# l297_l298.net
KiCad netlist of a schematic drawn in Altium Designer
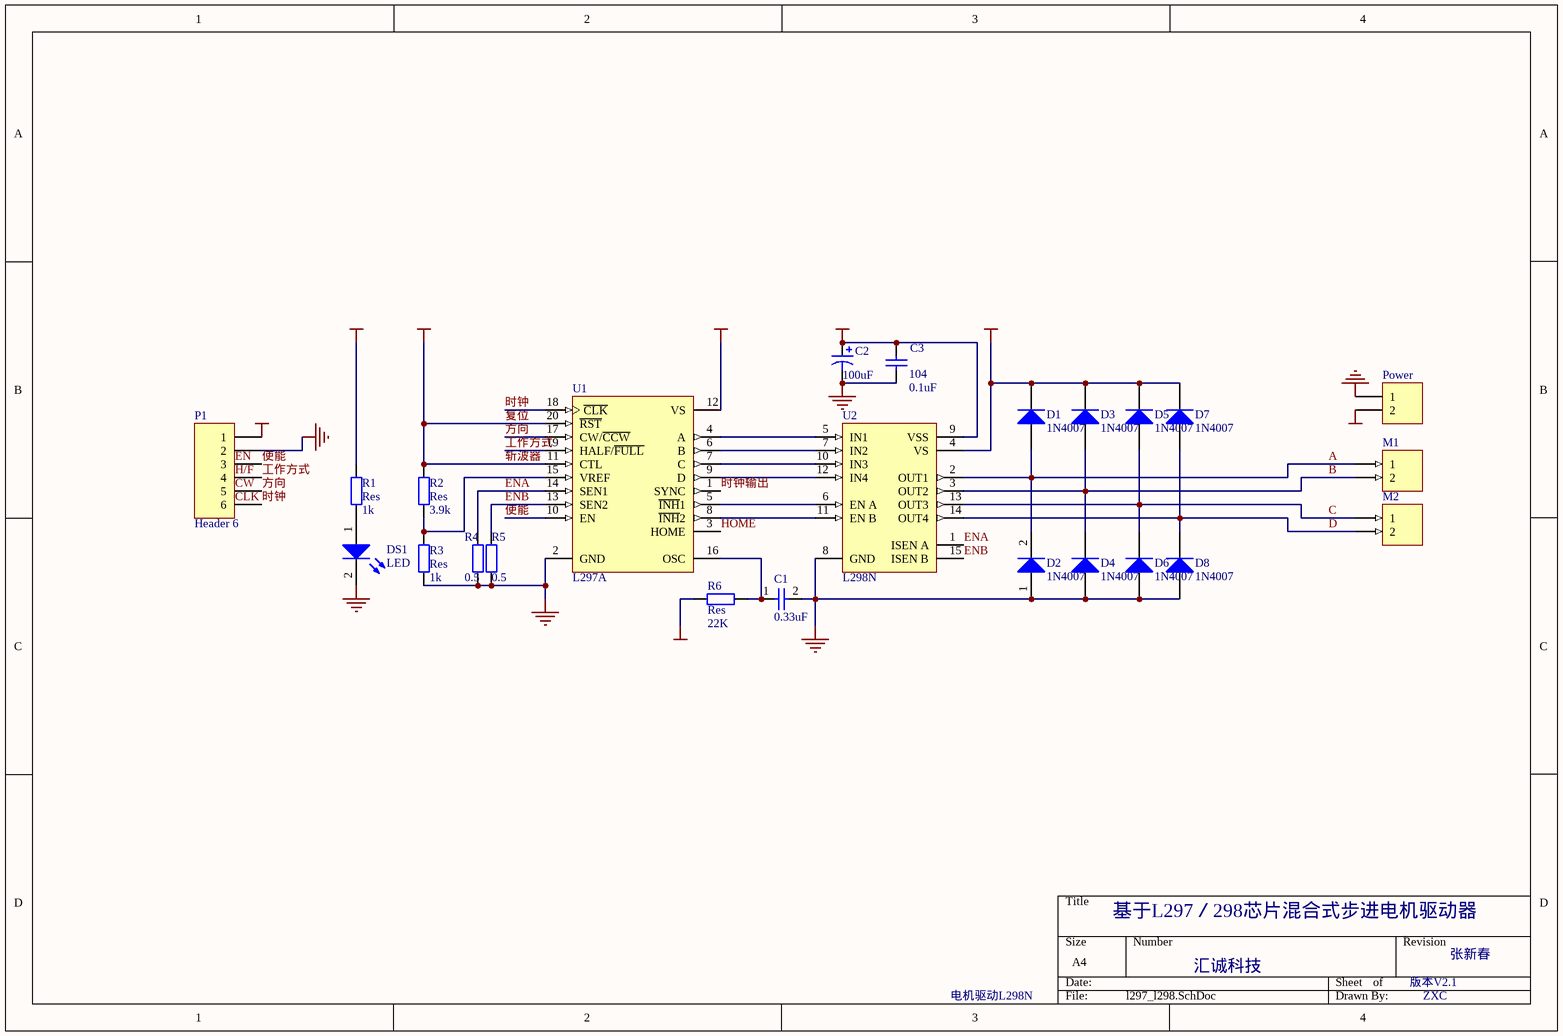
[diagram p0: l297_l298.SchDoc]

(export (version "E")
  (design (tool "Eeschema 10.0.6"))
  (components
    (comp (ref "C1")
      (value "0.33uF")
      (footprint "C-DJ-4")
      (description "Capacitor")
      (fields (field (name "PUBLISHER") "Altium Limited"))
      (libsource (lib "") (part "Cap_1"))
    )
    (comp (ref "C2")
      (value "100uF")
      (footprint "C-DJ-6")
      (description "Polarized Capacitor (Surface Mount)")
      (fields (field (name "PUBLISHER") "Altium Limited"))
      (libsource (lib "Miscellaneous Devices") (part "Cap Pol3"))
    )
    (comp (ref "C3")
      (value "104")
      (footprint "CPDR")
      (description "Capacitor")
      (fields (field (name "ALTIUM_VALUE") "0.1uF") (field (name "PUBLISHER") "Altium Limited"))
      (libsource (lib "Miscellaneous Devices") (part "Cap"))
    )
    (comp (ref "D1")
      (value "1N4007")
      (footprint "D-ZL-10")
      (description "1 Amp General Purpose Rectifier")
      (fields (field (name "PUBLISHER") "Altium Limited"))
      (libsource (lib "Miscellaneous Devices") (part "Diode 1N4007"))
    )
    (comp (ref "D2")
      (value "1N4007")
      (footprint "D-ZL-10")
      (description "1 Amp General Purpose Rectifier")
      (fields (field (name "PUBLISHER") "Altium Limited"))
      (libsource (lib "") (part "Diode 1N4007_1"))
    )
    (comp (ref "D3")
      (value "1N4007")
      (footprint "D-ZL-10")
      (description "1 Amp General Purpose Rectifier")
      (fields (field (name "PUBLISHER") "Altium Limited"))
      (libsource (lib "Miscellaneous Devices") (part "Diode 1N4007"))
    )
    (comp (ref "D4")
      (value "1N4007")
      (footprint "D-ZL-10")
      (description "1 Amp General Purpose Rectifier")
      (fields (field (name "PUBLISHER") "Altium Limited"))
      (libsource (lib "Miscellaneous Devices") (part "Diode 1N4007"))
    )
    (comp (ref "D5")
      (value "1N4007")
      (footprint "D-ZL-10")
      (description "1 Amp General Purpose Rectifier")
      (fields (field (name "PUBLISHER") "Altium Limited"))
      (libsource (lib "Miscellaneous Devices") (part "Diode 1N4007"))
    )
    (comp (ref "D6")
      (value "1N4007")
      (footprint "D-ZL-10")
      (description "1 Amp General Purpose Rectifier")
      (fields (field (name "PUBLISHER") "Altium Limited"))
      (libsource (lib "Miscellaneous Devices") (part "Diode 1N4007"))
    )
    (comp (ref "D7")
      (value "1N4007")
      (footprint "D-ZL-10")
      (description "1 Amp General Purpose Rectifier")
      (fields (field (name "PUBLISHER") "Altium Limited"))
      (libsource (lib "Miscellaneous Devices") (part "Diode 1N4007"))
    )
    (comp (ref "D8")
      (value "1N4007")
      (footprint "D-ZL-10")
      (description "1 Amp General Purpose Rectifier")
      (fields (field (name "PUBLISHER") "Altium Limited"))
      (libsource (lib "Miscellaneous Devices") (part "Diode 1N4007"))
    )
    (comp (ref "DS1")
      (value "LED")
      (footprint "CPDR")
      (description "发光二极管")
      (fields (field (name "PUBLISHER") "Altium Limited"))
      (libsource (lib "zxcourhc") (part "LED"))
    )
    (comp (ref "M1")
      (value "~")
      (footprint "JK128_2")
      (description "Header, 2-Pin")
      (fields (field (name "PUBLISHER") "Altium Limited"))
      (libsource (lib "Miscellaneous Connectors") (part "MHDR1X2"))
    )
    (comp (ref "M2")
      (value "~")
      (footprint "JK128_2")
      (description "Header, 2-Pin")
      (fields (field (name "PUBLISHER") "Altium Limited"))
      (libsource (lib "Miscellaneous Connectors") (part "MHDR1X2"))
    )
    (comp (ref "P1")
      (value "Header 6")
      (footprint "HDR1X6")
      (description "Header, 6-Pin")
      (fields (field (name "PUBLISHER") "Altium Limited"))
      (libsource (lib "Miscellaneous Connectors") (part "Header 6"))
    )
    (comp (ref "Power")
      (value "~")
      (footprint "JK128_2")
      (description "Header, 2-Pin")
      (fields (field (name "PUBLISHER") "Altium Limited"))
      (libsource (lib "Miscellaneous Connectors") (part "MHDR1X2"))
    )
    (comp (ref "R1")
      (value "Res")
      (footprint "zxcourhc:CPDR")
      (description "电阻")
      (fields (field (name "ALTIUM_VALUE") "1k") (field (name "PUBLISHER") "Altium Limited"))
      (libsource (lib "zxcourhc") (part "Res"))
    )
    (comp (ref "R2")
      (value "Res")
      (footprint "zxcourhc:CPDR")
      (description "电阻")
      (fields (field (name "ALTIUM_VALUE") "3.9k") (field (name "PUBLISHER") "Altium Limited"))
      (libsource (lib "zxcourhc") (part "Res"))
    )
    (comp (ref "R3")
      (value "Res")
      (footprint "CPDR")
      (description "电阻")
      (fields (field (name "ALTIUM_VALUE") "1k") (field (name "PUBLISHER") "Altium Limited"))
      (libsource (lib "zxcourhc") (part "Res"))
    )
    (comp (ref "R4")
      (value "0.5")
      (footprint "ZCDZl")
      (description "电阻")
      (fields (field (name "PUBLISHER") "Altium Limited"))
      (libsource (lib "zxcourhc") (part "Res"))
    )
    (comp (ref "R5")
      (value "0.5")
      (footprint "ZCDZl")
      (description "电阻")
      (fields (field (name "PUBLISHER") "Altium Limited"))
      (libsource (lib "zxcourhc") (part "Res"))
    )
    (comp (ref "R6")
      (value "Res")
      (footprint "CPDR")
      (description "电阻")
      (fields (field (name "ALTIUM_VALUE") "22K") (field (name "PUBLISHER") "Altium Limited"))
      (libsource (lib "") (part "Res_1"))
    )
    (comp (ref "U1")
      (value "L297A")
      (footprint "DIP-20")
      (description "Stepper Motor Controller")
      (fields (field (name "PUBLISHER") "Altium Limited"))
      (libsource (lib "ST Interface Stepper Motor Controller") (part "L297A"))
    )
    (comp (ref "U2")
      (value "L298N")
      (footprint "zxcourhc:L298N")
      (description "Dual Full Bridge Driver")
      (fields (field (name "PUBLISHER") "Altium Limited"))
      (libsource (lib "ST Interface DC Motor Controller") (part "L298N"))
    )
  )
  (nets
    (net (code "1") (name "+5V") (class "Default")
      (node (ref "C2") (pin "1") (pinfunction "1_1") (pintype "passive"))
      (node (ref "C3") (pin "2") (pinfunction "2_2") (pintype "passive"))
      (node (ref "P1") (pin "1") (pinfunction "1_1") (pintype "passive"))
      (node (ref "R1") (pin "1") (pinfunction "1_1") (pintype "passive"))
      (node (ref "R2") (pin "1") (pinfunction "1_1") (pintype "passive"))
      (node (ref "R6") (pin "2") (pinfunction "2_2") (pintype "passive"))
      (node (ref "U1") (pin "11") (pinfunction "CTL_11") (pintype "input"))
      (node (ref "U1") (pin "12") (pinfunction "VS_12") (pintype "power_in"))
      (node (ref "U1") (pin "20") (pinfunction "~{RST}_20") (pintype "input"))
      (node (ref "U2") (pin "9") (pinfunction "VSS_9") (pintype "power_in"))
    )
    (net (code "2") (name "/A") (class "Default")
      (node (ref "D1") (pin "1") (pinfunction "A_1") (pintype "passive"))
      (node (ref "D2") (pin "2") (pinfunction "K_2") (pintype "passive"))
      (node (ref "M1") (pin "1") (pinfunction "1_1") (pintype "power_in"))
      (node (ref "U2") (pin "2") (pinfunction "OUT1_2") (pintype "output"))
    )
    (net (code "3") (name "/B") (class "Default")
      (node (ref "D3") (pin "1") (pinfunction "A_1") (pintype "passive"))
      (node (ref "D4") (pin "2") (pinfunction "K_2") (pintype "passive"))
      (node (ref "M1") (pin "2") (pinfunction "2_2") (pintype "power_in"))
      (node (ref "U2") (pin "3") (pinfunction "OUT2_3") (pintype "output"))
    )
    (net (code "4") (name "/C") (class "Default")
      (node (ref "D5") (pin "1") (pinfunction "A_1") (pintype "passive"))
      (node (ref "D6") (pin "2") (pinfunction "K_2") (pintype "passive"))
      (node (ref "M2") (pin "1") (pinfunction "1_1") (pintype "power_in"))
      (node (ref "U2") (pin "13") (pinfunction "OUT3_13") (pintype "output"))
    )
    (net (code "7") (name "/D") (class "Default")
      (node (ref "D7") (pin "1") (pinfunction "A_1") (pintype "passive"))
      (node (ref "D8") (pin "2") (pinfunction "K_2") (pintype "passive"))
      (node (ref "M2") (pin "2") (pinfunction "2_2") (pintype "power_in"))
      (node (ref "U2") (pin "14") (pinfunction "OUT4_14") (pintype "output"))
    )
    (net (code "9") (name "/ENA") (class "Default")
      (node (ref "R4") (pin "1") (pinfunction "1_1") (pintype "passive"))
      (node (ref "U1") (pin "14") (pinfunction "SEN1_14") (pintype "input"))
      (node (ref "U2") (pin "1") (pinfunction "ISEN_A_1") (pintype "passive"))
    )
    (net (code "10") (name "/ENB") (class "Default")
      (node (ref "R5") (pin "1") (pinfunction "1_1") (pintype "passive"))
      (node (ref "U1") (pin "13") (pinfunction "SEN2_13") (pintype "input"))
      (node (ref "U2") (pin "15") (pinfunction "ISEN_B_15") (pintype "passive"))
    )
    (net (code "11") (name "/HOME") (class "Default")
      (node (ref "U1") (pin "3") (pinfunction "HOME_3") (pintype "open_collector"))
    )
    (net (code "13") (name "/使能") (class "Default")
      (node (ref "P1") (pin "3") (pinfunction "3_3") (pintype "passive"))
      (node (ref "U1") (pin "10") (pinfunction "EN_10") (pintype "input"))
    )
    (net (code "14") (name "/工作方式") (class "Default")
      (node (ref "P1") (pin "4") (pinfunction "4_4") (pintype "passive"))
      (node (ref "U1") (pin "19") (pinfunction "HALF/~{FULL}_19") (pintype "input"))
    )
    (net (code "15") (name "/方向") (class "Default")
      (node (ref "P1") (pin "5") (pinfunction "5_5") (pintype "passive"))
      (node (ref "U1") (pin "17") (pinfunction "CW/~{CCW}_17") (pintype "input"))
    )
    (net (code "16") (name "/时钟") (class "Default")
      (node (ref "P1") (pin "6") (pinfunction "6_6") (pintype "passive"))
      (node (ref "U1") (pin "18") (pinfunction "~{CLK}_18") (pintype "input"))
    )
    (net (code "17") (name "/时钟输出") (class "Default")
      (node (ref "U1") (pin "1") (pinfunction "SYNC_1") (pintype "output"))
    )
    (net (code "18") (name "GND") (class "Default")
      (node (ref "C1") (pin "2") (pinfunction "2_2") (pintype "passive"))
      (node (ref "C2") (pin "2") (pinfunction "2_2") (pintype "passive"))
      (node (ref "C3") (pin "1") (pinfunction "1_1") (pintype "passive"))
      (node (ref "D2") (pin "1") (pinfunction "A_1") (pintype "passive"))
      (node (ref "D4") (pin "1") (pinfunction "A_1") (pintype "passive"))
      (node (ref "D6") (pin "1") (pinfunction "A_1") (pintype "passive"))
      (node (ref "D8") (pin "1") (pinfunction "A_1") (pintype "passive"))
      (node (ref "DS1") (pin "2") (pinfunction "K_2") (pintype "passive"))
      (node (ref "P1") (pin "2") (pinfunction "2_2") (pintype "passive"))
      (node (ref "Power") (pin "1") (pinfunction "1_1") (pintype "power_in"))
      (node (ref "R3") (pin "2") (pinfunction "2_2") (pintype "passive"))
      (node (ref "R4") (pin "2") (pinfunction "2_2") (pintype "passive"))
      (node (ref "R5") (pin "2") (pinfunction "2_2") (pintype "passive"))
      (node (ref "U1") (pin "2") (pinfunction "GND_2") (pintype "power_in"))
      (node (ref "U2") (pin "8") (pinfunction "GND_8") (pintype "power_in"))
    )
    (net (code "19") (name "Net-(DS1-A)") (class "Default")
      (node (ref "DS1") (pin "1") (pinfunction "A_1") (pintype "passive"))
      (node (ref "R1") (pin "2") (pinfunction "2_2") (pintype "passive"))
    )
    (net (code "20") (name "Net-(U1-A)") (class "Default")
      (node (ref "U1") (pin "4") (pinfunction "A_4") (pintype "output"))
      (node (ref "U2") (pin "5") (pinfunction "IN1_5") (pintype "input"))
    )
    (net (code "21") (name "Net-(U1-B)") (class "Default")
      (node (ref "U1") (pin "6") (pinfunction "B_6") (pintype "output"))
      (node (ref "U2") (pin "7") (pinfunction "IN2_7") (pintype "input"))
    )
    (net (code "22") (name "Net-(U1-C)") (class "Default")
      (node (ref "U1") (pin "7") (pinfunction "C_7") (pintype "output"))
      (node (ref "U2") (pin "10") (pinfunction "IN3_10") (pintype "input"))
    )
    (net (code "23") (name "Net-(U1-D)") (class "Default")
      (node (ref "U1") (pin "9") (pinfunction "D_9") (pintype "output"))
      (node (ref "U2") (pin "12") (pinfunction "IN4_12") (pintype "input"))
    )
    (net (code "24") (name "Net-(U1-OSC)") (class "Default")
      (node (ref "C1") (pin "1") (pinfunction "1_1") (pintype "passive"))
      (node (ref "R6") (pin "1") (pinfunction "1_1") (pintype "passive"))
      (node (ref "U1") (pin "16") (pinfunction "OSC_16") (pintype "passive"))
    )
    (net (code "25") (name "Net-(U1-VREF)") (class "Default")
      (node (ref "R2") (pin "2") (pinfunction "2_2") (pintype "passive"))
      (node (ref "R3") (pin "1") (pinfunction "1_1") (pintype "passive"))
      (node (ref "U1") (pin "15") (pinfunction "VREF_15") (pintype "input"))
    )
    (net (code "26") (name "Net-(U1-~{INH}1)") (class "Default")
      (node (ref "U1") (pin "5") (pinfunction "~{INH}1_5") (pintype "output"))
      (node (ref "U2") (pin "6") (pinfunction "EN_A_6") (pintype "input"))
    )
    (net (code "27") (name "Net-(U1-~{INH}2)") (class "Default")
      (node (ref "U1") (pin "8") (pinfunction "~{INH}2_8") (pintype "output"))
      (node (ref "U2") (pin "11") (pinfunction "EN_B_11") (pintype "input"))
    )
    (net (code "28") (name "VCC") (class "Default")
      (node (ref "D1") (pin "2") (pinfunction "K_2") (pintype "passive"))
      (node (ref "D3") (pin "2") (pinfunction "K_2") (pintype "passive"))
      (node (ref "D5") (pin "2") (pinfunction "K_2") (pintype "passive"))
      (node (ref "D7") (pin "2") (pinfunction "K_2") (pintype "passive"))
      (node (ref "Power") (pin "2") (pinfunction "2_2") (pintype "power_in"))
      (node (ref "U2") (pin "4") (pinfunction "VS_4") (pintype "power_in"))
    )
  )
)
